# easiri.net
KiCad netlist of a schematic drawn in EAGLE
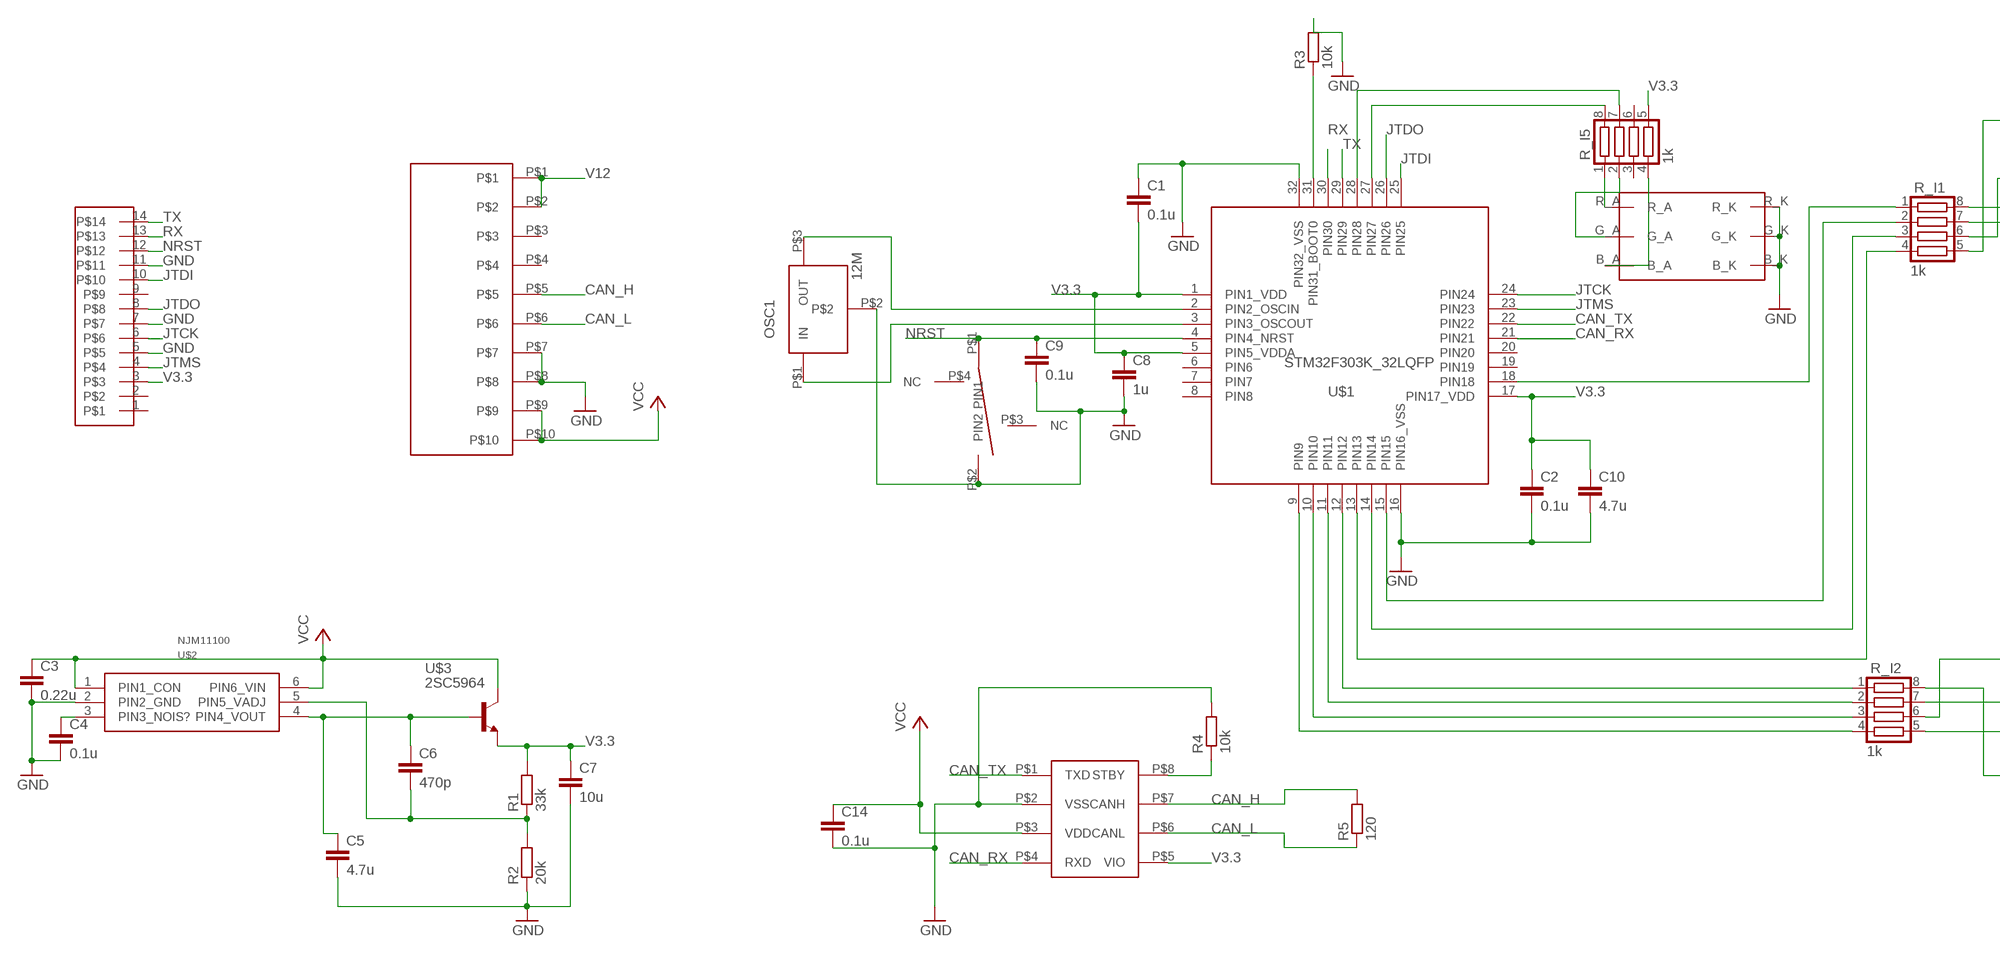
[diagram p0: schematic, sheet 1, part 1 of 2]
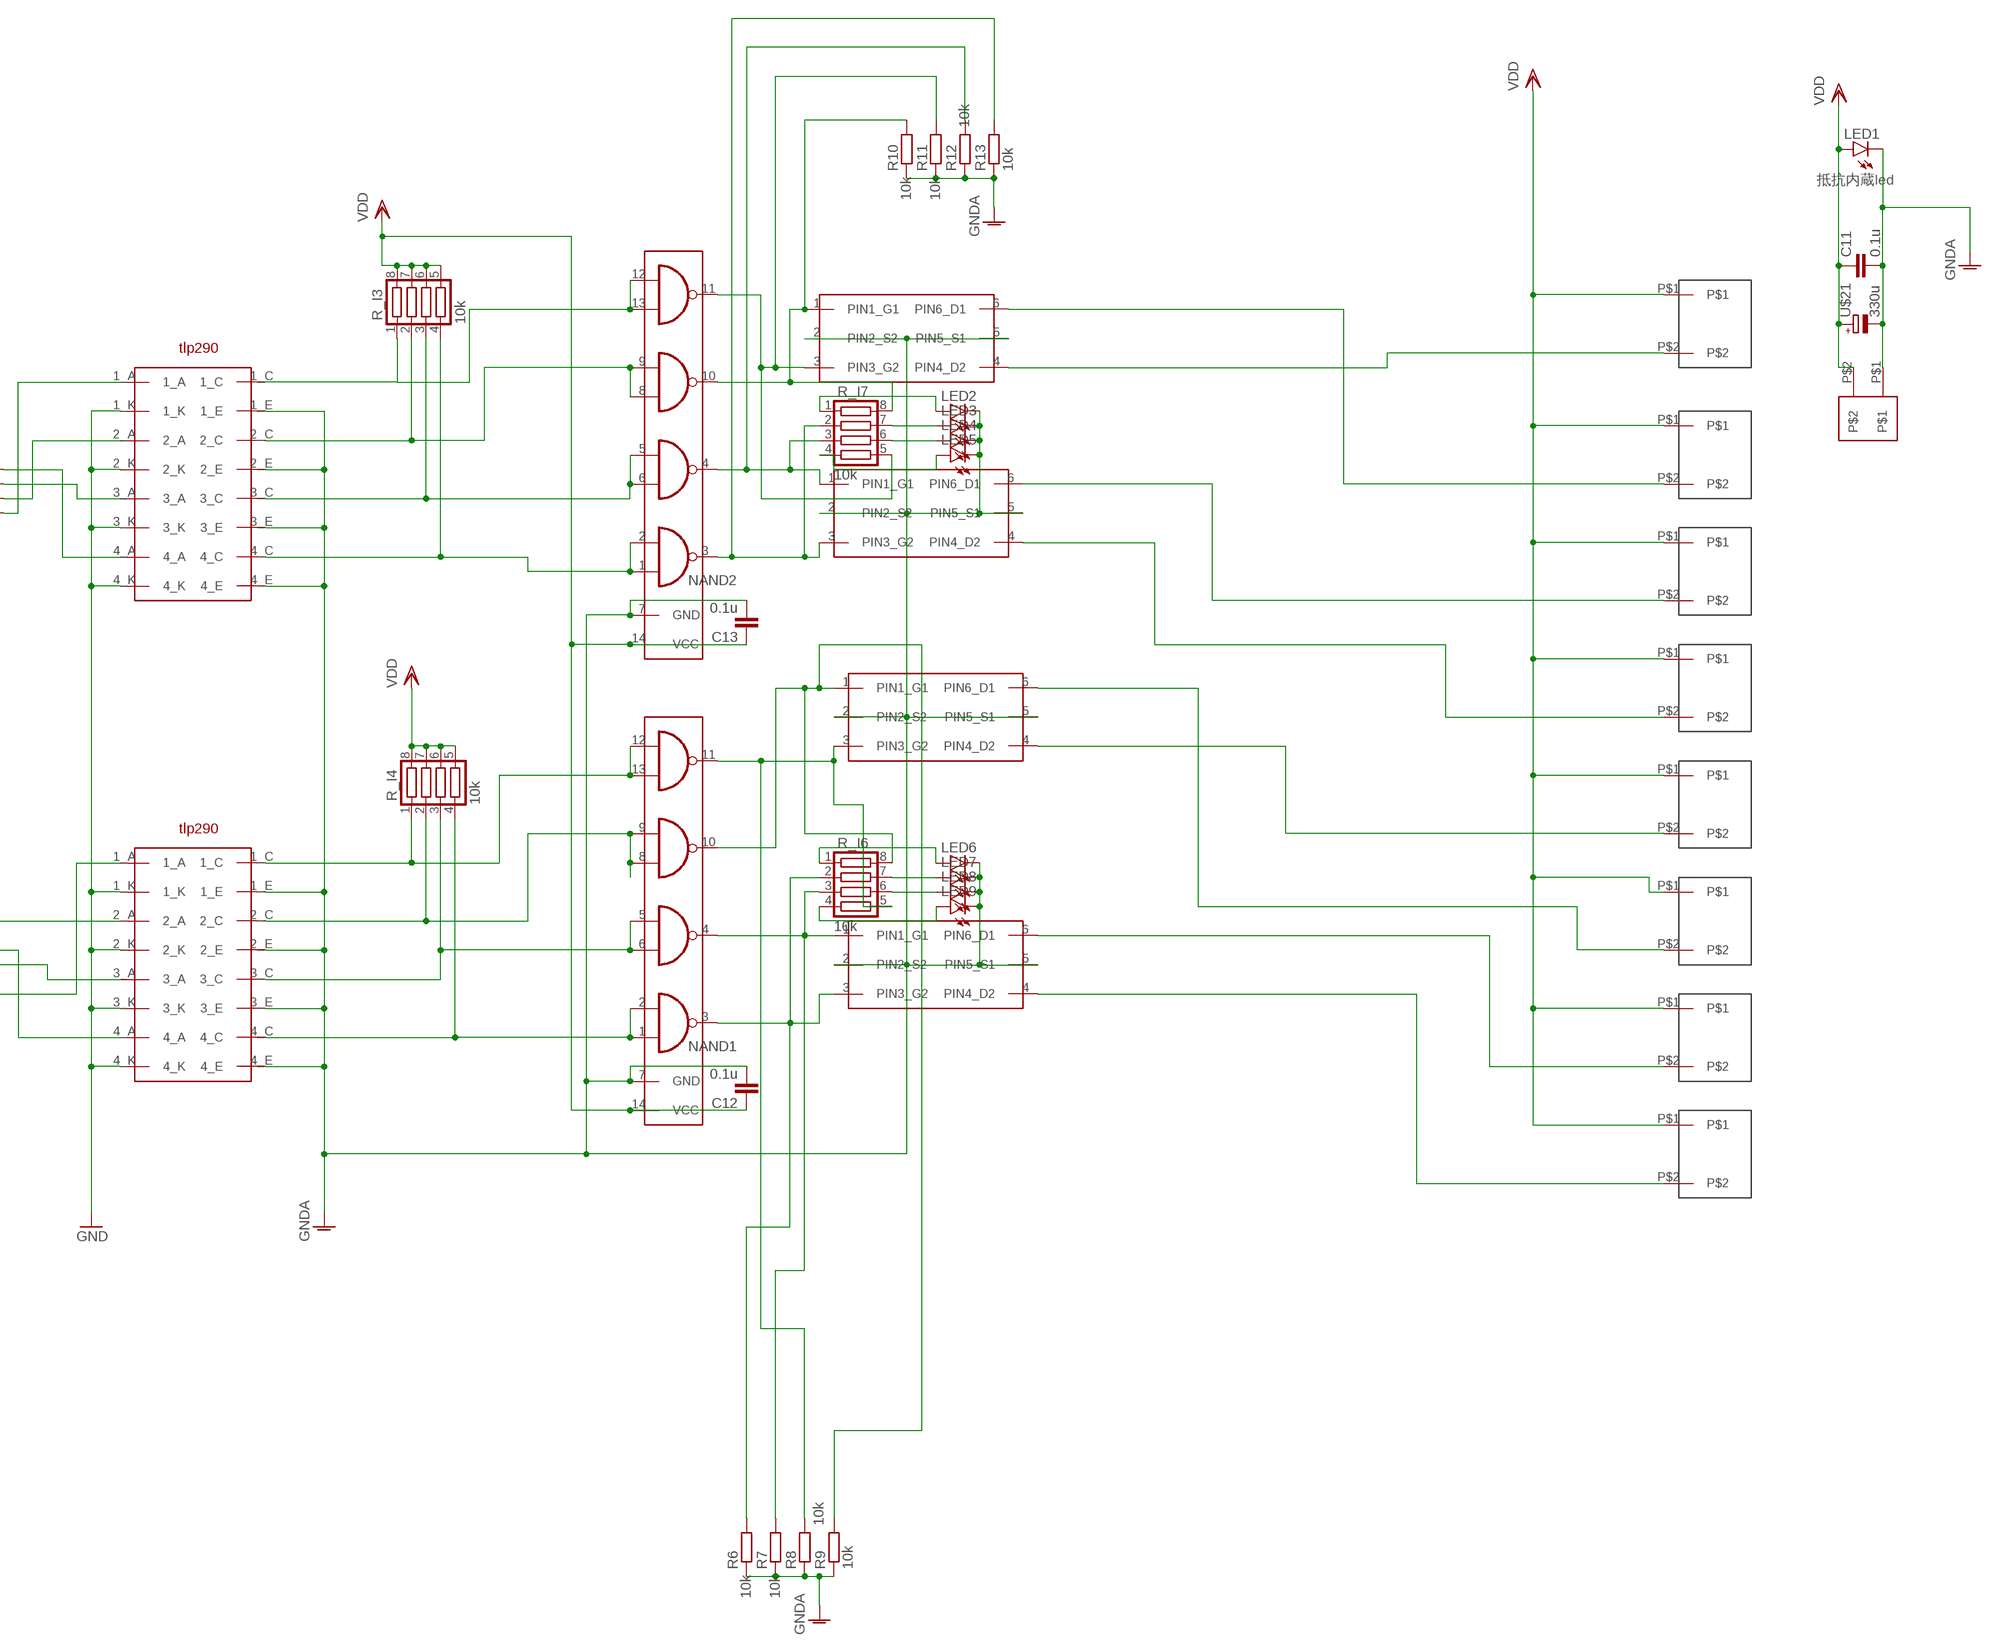
[diagram p1: schematic, sheet 1, part 2 of 2]

(export (version "E")
  (design (tool "Eeschema 10.0.6"))
  (components
    (comp (ref "BOX10P-L2")
      (value "BOX10PBOX10P-L")
      (footprint "eagle-import:BOX10P-L")
      (libsource (lib "eagle-import") (part "BOX10PBOX10P-L"))
    )
    (comp (ref "C1")
      (value "0.1u")
      (footprint "eagle-import:C1608")
      (libsource (lib "eagle-import") (part "C-EUC1608"))
    )
    (comp (ref "C2")
      (value "0.1u")
      (footprint "eagle-import:C1608")
      (libsource (lib "eagle-import") (part "C-EUC1608"))
    )
    (comp (ref "C3")
      (value "0.22u")
      (footprint "eagle-import:C2012")
      (libsource (lib "eagle-import") (part "C-EUC2012"))
    )
    (comp (ref "C4")
      (value "0.1u")
      (footprint "eagle-import:C1608")
      (libsource (lib "eagle-import") (part "C-EUC1608"))
    )
    (comp (ref "C5")
      (value "4.7u")
      (footprint "eagle-import:C2012")
      (libsource (lib "eagle-import") (part "C-EUC2012"))
    )
    (comp (ref "C6")
      (value "470p")
      (footprint "eagle-import:C1608")
      (libsource (lib "eagle-import") (part "C-EUC1608"))
    )
    (comp (ref "C7")
      (value "10u")
      (footprint "eagle-import:C2012")
      (libsource (lib "eagle-import") (part "C-EUC2012"))
    )
    (comp (ref "C8")
      (value "1u")
      (footprint "eagle-import:C1608")
      (libsource (lib "eagle-import") (part "C-EUC1608"))
    )
    (comp (ref "C9")
      (value "0.1u")
      (footprint "eagle-import:C1608")
      (libsource (lib "eagle-import") (part "C-EUC1608"))
    )
    (comp (ref "C10")
      (value "4.7u")
      (footprint "eagle-import:C2012")
      (libsource (lib "eagle-import") (part "C-EUC2012"))
    )
    (comp (ref "C11")
      (value "0.1u")
      (footprint "eagle-import:C1608")
      (libsource (lib "eagle-import") (part "C-EUC1608"))
    )
    (comp (ref "C12")
      (value "0.1u")
      (footprint "eagle-import:C1608")
      (libsource (lib "eagle-import") (part "C-EUC1608"))
    )
    (comp (ref "C13")
      (value "0.1u")
      (footprint "eagle-import:C1608")
      (libsource (lib "eagle-import") (part "C-EUC1608"))
    )
    (comp (ref "C14")
      (value "0.1u")
      (footprint "eagle-import:C1608")
      (libsource (lib "eagle-import") (part "C-EUC1608"))
    )
    (comp (ref "ES1")
      (value "XH_2P")
      (footprint "eagle-import:XH_2P")
      (libsource (lib "eagle-import") (part "XH_2P"))
    )
    (comp (ref "ES2")
      (value "XH_2P")
      (footprint "eagle-import:XH_2P")
      (libsource (lib "eagle-import") (part "XH_2P"))
    )
    (comp (ref "ES3")
      (value "XH_2P")
      (footprint "eagle-import:XH_2P")
      (libsource (lib "eagle-import") (part "XH_2P"))
    )
    (comp (ref "ES4")
      (value "XH_2P")
      (footprint "eagle-import:XH_2P")
      (libsource (lib "eagle-import") (part "XH_2P"))
    )
    (comp (ref "ES5")
      (value "XH_2P")
      (footprint "eagle-import:XH_2P")
      (libsource (lib "eagle-import") (part "XH_2P"))
    )
    (comp (ref "ES6")
      (value "XH_2P")
      (footprint "eagle-import:XH_2P")
      (libsource (lib "eagle-import") (part "XH_2P"))
    )
    (comp (ref "ES7")
      (value "XH_2P")
      (footprint "eagle-import:XH_2P")
      (libsource (lib "eagle-import") (part "XH_2P"))
    )
    (comp (ref "ES8")
      (value "XH_2P")
      (footprint "eagle-import:XH_2P")
      (libsource (lib "eagle-import") (part "XH_2P"))
    )
    (comp (ref "LED1")
      (value "抵抗内蔵led")
      (footprint "eagle-import:LED5MM")
      (libsource (lib "eagle-import") (part "LED5MM"))
    )
    (comp (ref "LED2")
      (value "1608LED")
      (footprint "eagle-import:1608")
      (libsource (lib "eagle-import") (part "1608LED"))
    )
    (comp (ref "LED3")
      (value "1608LED")
      (footprint "eagle-import:1608")
      (libsource (lib "eagle-import") (part "1608LED"))
    )
    (comp (ref "LED4")
      (value "1608LED")
      (footprint "eagle-import:1608")
      (libsource (lib "eagle-import") (part "1608LED"))
    )
    (comp (ref "LED5")
      (value "1608LED")
      (footprint "eagle-import:1608")
      (libsource (lib "eagle-import") (part "1608LED"))
    )
    (comp (ref "LED6")
      (value "1608LED")
      (footprint "eagle-import:1608")
      (libsource (lib "eagle-import") (part "1608LED"))
    )
    (comp (ref "LED7")
      (value "1608LED")
      (footprint "eagle-import:1608")
      (libsource (lib "eagle-import") (part "1608LED"))
    )
    (comp (ref "LED8")
      (value "1608LED")
      (footprint "eagle-import:1608")
      (libsource (lib "eagle-import") (part "1608LED"))
    )
    (comp (ref "LED9")
      (value "1608LED")
      (footprint "eagle-import:1608")
      (libsource (lib "eagle-import") (part "1608LED"))
    )
    (comp (ref "NAND1")
      (value "14PIN_NAND2")
      (footprint "eagle-import:TSSOP14")
      (libsource (lib "eagle-import") (part "14PIN_NAND2"))
    )
    (comp (ref "NAND2")
      (value "14PIN_NAND2")
      (footprint "eagle-import:TSSOP14")
      (libsource (lib "eagle-import") (part "14PIN_NAND2"))
    )
    (comp (ref "OSC1")
      (value "12M")
      (footprint "eagle-import:CSTNE#")
      (libsource (lib "eagle-import") (part "CSTN#"))
    )
    (comp (ref "R1")
      (value "33k")
      (footprint "eagle-import:1608")
      (libsource (lib "eagle-import") (part "R_REG"))
    )
    (comp (ref "R2")
      (value "20k")
      (footprint "eagle-import:1608")
      (libsource (lib "eagle-import") (part "R_REG"))
    )
    (comp (ref "R3")
      (value "10k")
      (footprint "eagle-import:1608")
      (libsource (lib "eagle-import") (part "R_REG"))
    )
    (comp (ref "R4")
      (value "10k")
      (footprint "eagle-import:1608")
      (libsource (lib "eagle-import") (part "R_REG"))
    )
    (comp (ref "R5")
      (value "120")
      (footprint "eagle-import:1608")
      (libsource (lib "eagle-import") (part "R_REG"))
    )
    (comp (ref "R6")
      (value "10k")
      (footprint "eagle-import:1608")
      (libsource (lib "eagle-import") (part "R_REG"))
    )
    (comp (ref "R7")
      (value "10k")
      (footprint "eagle-import:1608")
      (libsource (lib "eagle-import") (part "R_REG"))
    )
    (comp (ref "R8")
      (value "10k")
      (footprint "eagle-import:1608")
      (libsource (lib "eagle-import") (part "R_REG"))
    )
    (comp (ref "R9")
      (value "10k")
      (footprint "eagle-import:1608")
      (libsource (lib "eagle-import") (part "R_REG"))
    )
    (comp (ref "R10")
      (value "10k")
      (footprint "eagle-import:1608")
      (libsource (lib "eagle-import") (part "R_REG"))
    )
    (comp (ref "R11")
      (value "10k")
      (footprint "eagle-import:1608")
      (libsource (lib "eagle-import") (part "R_REG"))
    )
    (comp (ref "R12")
      (value "10k")
      (footprint "eagle-import:1608")
      (libsource (lib "eagle-import") (part "R_REG"))
    )
    (comp (ref "R13")
      (value "10k")
      (footprint "eagle-import:1608")
      (libsource (lib "eagle-import") (part "R_REG"))
    )
    (comp (ref "R_I1")
      (value "1k")
      (footprint "eagle-import:0603X4RESISTOR")
      (libsource (lib "eagle-import") (part "R_SHUGOU"))
    )
    (comp (ref "R_I2")
      (value "1k")
      (footprint "eagle-import:0603X4RESISTOR")
      (libsource (lib "eagle-import") (part "R_SHUGOU"))
    )
    (comp (ref "R_I3")
      (value "10k")
      (footprint "eagle-import:1005X4RESISTOR")
      (libsource (lib "eagle-import") (part "R_SHUGOU2"))
    )
    (comp (ref "R_I4")
      (value "10k")
      (footprint "eagle-import:1005X4RESISTOR")
      (libsource (lib "eagle-import") (part "R_SHUGOU2"))
    )
    (comp (ref "R_I5")
      (value "1k")
      (footprint "eagle-import:0603X4RESISTOR")
      (libsource (lib "eagle-import") (part "R_SHUGOU"))
    )
    (comp (ref "R_I6")
      (value "10k")
      (footprint "eagle-import:1005X4RESISTOR")
      (libsource (lib "eagle-import") (part "R_SHUGOU2"))
    )
    (comp (ref "R_I7")
      (value "10k")
      (footprint "eagle-import:1005X4RESISTOR")
      (libsource (lib "eagle-import") (part "R_SHUGOU2"))
    )
    (comp (ref "U$1")
      (value "STM32F303K_32LQFP")
      (footprint "eagle-import:LQFP32-7X7")
      (libsource (lib "eagle-import") (part "STM32F303K_32LQFP"))
    )
    (comp (ref "U$2")
      (value "NJM11100")
      (footprint "eagle-import:SOT23-6")
      (libsource (lib "eagle-import") (part "NJM11100"))
    )
    (comp (ref "U$3")
      (value "2SC5964")
      (footprint "eagle-import:PCP")
      (libsource (lib "eagle-import") (part "2SC5964"))
    )
    (comp (ref "U$4")
      (value "TAKUTOSUITTI2")
      (footprint "eagle-import:TAKUTOSUITTI2")
      (libsource (lib "eagle-import") (part "TAKUTOSUITTI2"))
    )
    (comp (ref "U$5")
      (value "MCP2562MCP2561-SN")
      (footprint "eagle-import:SOIC8")
      (libsource (lib "eagle-import") (part "MCP2562MCP2561-SN"))
    )
    (comp (ref "U$6")
      (value "TLP290-4")
      (footprint "eagle-import:TLP290")
      (libsource (lib "eagle-import") (part "TLP290-4"))
    )
    (comp (ref "U$7")
      (value "TLP290-4")
      (footprint "eagle-import:TLP290")
      (libsource (lib "eagle-import") (part "TLP290-4"))
    )
    (comp (ref "U$8")
      (value "SSOT6_FET")
      (footprint "eagle-import:SSOT6")
      (libsource (lib "eagle-import") (part "SSOT6_FET"))
    )
    (comp (ref "U$9")
      (value "SSOT6_FET")
      (footprint "eagle-import:SSOT6")
      (libsource (lib "eagle-import") (part "SSOT6_FET"))
    )
    (comp (ref "U$10")
      (value "SSOT6_FET")
      (footprint "eagle-import:SSOT6")
      (libsource (lib "eagle-import") (part "SSOT6_FET"))
    )
    (comp (ref "U$11")
      (value "SSOT6_FET")
      (footprint "eagle-import:SSOT6")
      (libsource (lib "eagle-import") (part "SSOT6_FET"))
    )
    (comp (ref "U$12")
      (value "YUROBLOCK2")
      (footprint "eagle-import:YUROBLOCK2")
      (libsource (lib "eagle-import") (part "YUROBLOCK2"))
    )
    (comp (ref "U$21")
      (value "330u")
      (footprint "eagle-import:1014CAPA")
      (libsource (lib "eagle-import") (part "C_DEKAI"))
    )
    (comp (ref "U$22")
      (value "BOX14P")
      (footprint "eagle-import:CON_HEDA14P_1.27")
      (libsource (lib "eagle-import") (part "BOX14P"))
    )
    (comp (ref "U$23")
      (value "RGB_LED")
      (footprint "eagle-import:RGB_LED")
      (libsource (lib "eagle-import") (part "RGB_LED"))
    )
  )
  (nets
    (net (code "1") (name "/CAN_H") (class "Default")
      (node (ref "BOX10P-L2") (pin "P$5") (pinfunction "P$5_P$5") (pintype "bidirectional"))
      (node (ref "R5") (pin "2") (pinfunction "2_2") (pintype "passive"))
      (node (ref "U$5") (pin "P$7") (pinfunction "CANH_P$7") (pintype "bidirectional"))
    )
    (net (code "2") (name "/CAN_L") (class "Default")
      (node (ref "BOX10P-L2") (pin "P$6") (pinfunction "P$6_P$6") (pintype "bidirectional"))
      (node (ref "R5") (pin "1") (pinfunction "1_1") (pintype "passive"))
      (node (ref "U$5") (pin "P$6") (pinfunction "CANL_P$6") (pintype "bidirectional"))
    )
    (net (code "3") (name "/CAN_RX") (class "Default")
      (node (ref "U$1") (pin "21") (pinfunction "PIN21_21") (pintype "bidirectional"))
      (node (ref "U$5") (pin "P$4") (pinfunction "RXD_P$4") (pintype "bidirectional"))
    )
    (net (code "4") (name "/CAN_TX") (class "Default")
      (node (ref "U$1") (pin "22") (pinfunction "PIN22_22") (pintype "bidirectional"))
      (node (ref "U$5") (pin "P$1") (pinfunction "TXD_P$1") (pintype "bidirectional"))
    )
    (net (code "5") (name "/JTCK") (class "Default")
      (node (ref "U$1") (pin "24") (pinfunction "PIN24_24") (pintype "bidirectional"))
      (node (ref "U$22") (pin "6") (pinfunction "P$6_6") (pintype "bidirectional"))
    )
    (net (code "6") (name "/JTDI") (class "Default")
      (node (ref "U$1") (pin "25") (pinfunction "PIN25_25") (pintype "bidirectional"))
      (node (ref "U$22") (pin "10") (pinfunction "P$10_10") (pintype "bidirectional"))
    )
    (net (code "7") (name "/JTDO") (class "Default")
      (node (ref "U$1") (pin "26") (pinfunction "PIN26_26") (pintype "bidirectional"))
      (node (ref "U$22") (pin "8") (pinfunction "P$8_8") (pintype "bidirectional"))
    )
    (net (code "8") (name "/JTMS") (class "Default")
      (node (ref "U$1") (pin "23") (pinfunction "PIN23_23") (pintype "bidirectional"))
      (node (ref "U$22") (pin "4") (pinfunction "P$4_4") (pintype "bidirectional"))
    )
    (net (code "9") (name "/NRST") (class "Default")
      (node (ref "C9") (pin "1") (pinfunction "1_1") (pintype "passive"))
      (node (ref "U$1") (pin "4") (pinfunction "PIN4_NRST_4") (pintype "bidirectional"))
      (node (ref "U$22") (pin "12") (pinfunction "P$12_12") (pintype "bidirectional"))
      (node (ref "U$4") (pin "P$1") (pinfunction "PIN1_P$1") (pintype "bidirectional"))
    )
    (net (code "10") (name "/RX") (class "Default")
      (node (ref "U$1") (pin "30") (pinfunction "PIN30_30") (pintype "bidirectional"))
      (node (ref "U$22") (pin "13") (pinfunction "P$13_13") (pintype "bidirectional"))
    )
    (net (code "11") (name "/TX") (class "Default")
      (node (ref "U$1") (pin "29") (pinfunction "PIN29_29") (pintype "bidirectional"))
      (node (ref "U$22") (pin "14") (pinfunction "P$14_14") (pintype "bidirectional"))
    )
    (net (code "12") (name "/V3.3") (class "Default")
      (node (ref "C1") (pin "2") (pinfunction "2_2") (pintype "passive"))
      (node (ref "C10") (pin "1") (pinfunction "1_1") (pintype "passive"))
      (node (ref "C2") (pin "1") (pinfunction "1_1") (pintype "passive"))
      (node (ref "C7") (pin "1") (pinfunction "1_1") (pintype "passive"))
      (node (ref "C8") (pin "1") (pinfunction "1_1") (pintype "passive"))
      (node (ref "R1") (pin "2") (pinfunction "2_2") (pintype "passive"))
      (node (ref "R_I5") (pin "5") (pinfunction "5_5") (pintype "passive"))
      (node (ref "U$1") (pin "1") (pinfunction "PIN1_VDD_1") (pintype "bidirectional"))
      (node (ref "U$1") (pin "17") (pinfunction "PIN17_VDD_17") (pintype "bidirectional"))
      (node (ref "U$1") (pin "5") (pinfunction "PIN5_VDDA_5") (pintype "bidirectional"))
      (node (ref "U$22") (pin "3") (pinfunction "P$3_3") (pintype "bidirectional"))
      (node (ref "U$3") (pin "3") (pinfunction "E_3") (pintype "passive"))
      (node (ref "U$5") (pin "P$5") (pinfunction "VIO_P$5") (pintype "bidirectional"))
    )
    (net (code "13") (name "/V12") (class "Default")
      (node (ref "BOX10P-L2") (pin "P$1") (pinfunction "P$1_P$1") (pintype "bidirectional"))
      (node (ref "BOX10P-L2") (pin "P$2") (pinfunction "P$2_P$2") (pintype "bidirectional"))
    )
    (net (code "14") (name "GND") (class "Default")
      (node (ref "BOX10P-L2") (pin "P$7") (pinfunction "P$7_P$7") (pintype "bidirectional"))
      (node (ref "BOX10P-L2") (pin "P$8") (pinfunction "P$8_P$8") (pintype "bidirectional"))
      (node (ref "C1") (pin "1") (pinfunction "1_1") (pintype "passive"))
      (node (ref "C10") (pin "2") (pinfunction "2_2") (pintype "passive"))
      (node (ref "C14") (pin "2") (pinfunction "2_2") (pintype "passive"))
      (node (ref "C2") (pin "2") (pinfunction "2_2") (pintype "passive"))
      (node (ref "C3") (pin "2") (pinfunction "2_2") (pintype "passive"))
      (node (ref "C4") (pin "2") (pinfunction "2_2") (pintype "passive"))
      (node (ref "C5") (pin "2") (pinfunction "2_2") (pintype "passive"))
      (node (ref "C7") (pin "2") (pinfunction "2_2") (pintype "passive"))
      (node (ref "C8") (pin "2") (pinfunction "2_2") (pintype "passive"))
      (node (ref "C9") (pin "2") (pinfunction "2_2") (pintype "passive"))
      (node (ref "OSC1") (pin "P$2") (pinfunction "P$2_P$2") (pintype "bidirectional"))
      (node (ref "R2") (pin "1") (pinfunction "1_1") (pintype "passive"))
      (node (ref "R3") (pin "2") (pinfunction "2_2") (pintype "passive"))
      (node (ref "R4") (pin "2") (pinfunction "2_2") (pintype "passive"))
      (node (ref "U$1") (pin "16") (pinfunction "PIN16_VSS_16") (pintype "bidirectional"))
      (node (ref "U$1") (pin "32") (pinfunction "PIN32_VSS_32") (pintype "bidirectional"))
      (node (ref "U$2") (pin "2") (pinfunction "PIN2_GND_2") (pintype "bidirectional"))
      (node (ref "U$22") (pin "11") (pinfunction "P$11_11") (pintype "bidirectional"))
      (node (ref "U$22") (pin "5") (pinfunction "P$5_5") (pintype "bidirectional"))
      (node (ref "U$22") (pin "7") (pinfunction "P$7_7") (pintype "bidirectional"))
      (node (ref "U$23") (pin "B_K") (pinfunction "B_K_B_K") (pintype "bidirectional"))
      (node (ref "U$23") (pin "G_K") (pinfunction "G_K_G_K") (pintype "bidirectional"))
      (node (ref "U$23") (pin "R_K") (pinfunction "R_K_R_K") (pintype "bidirectional"))
      (node (ref "U$4") (pin "P$2") (pinfunction "PIN2_P$2") (pintype "bidirectional"))
      (node (ref "U$5") (pin "P$2") (pinfunction "VSS_P$2") (pintype "bidirectional"))
      (node (ref "U$6") (pin "1_K") (pinfunction "1_K_1_K") (pintype "bidirectional"))
      (node (ref "U$6") (pin "2_K") (pinfunction "2_K_2_K") (pintype "bidirectional"))
      (node (ref "U$6") (pin "3_K") (pinfunction "3_K_3_K") (pintype "bidirectional"))
      (node (ref "U$6") (pin "4_K") (pinfunction "4_K_4_K") (pintype "bidirectional"))
      (node (ref "U$7") (pin "1_K") (pinfunction "1_K_1_K") (pintype "bidirectional"))
      (node (ref "U$7") (pin "2_K") (pinfunction "2_K_2_K") (pintype "bidirectional"))
      (node (ref "U$7") (pin "3_K") (pinfunction "3_K_3_K") (pintype "bidirectional"))
      (node (ref "U$7") (pin "4_K") (pinfunction "4_K_4_K") (pintype "bidirectional"))
    )
    (net (code "15") (name "GNDA") (class "Default")
      (node (ref "C11") (pin "2") (pinfunction "2_2") (pintype "passive"))
      (node (ref "C12") (pin "2") (pinfunction "2_2") (pintype "passive"))
      (node (ref "C13") (pin "2") (pinfunction "2_2") (pintype "passive"))
      (node (ref "LED1") (pin "K") (pinfunction "C_K") (pintype "passive"))
      (node (ref "LED2") (pin "K") (pinfunction "K_K") (pintype "passive"))
      (node (ref "LED3") (pin "K") (pinfunction "K_K") (pintype "passive"))
      (node (ref "LED4") (pin "K") (pinfunction "K_K") (pintype "passive"))
      (node (ref "LED5") (pin "K") (pinfunction "K_K") (pintype "passive"))
      (node (ref "LED6") (pin "K") (pinfunction "K_K") (pintype "passive"))
      (node (ref "LED7") (pin "K") (pinfunction "K_K") (pintype "passive"))
      (node (ref "LED8") (pin "K") (pinfunction "K_K") (pintype "passive"))
      (node (ref "LED9") (pin "K") (pinfunction "K_K") (pintype "passive"))
      (node (ref "NAND1") (pin "7") (pinfunction "GND_7") (pintype "bidirectional"))
      (node (ref "NAND2") (pin "7") (pinfunction "GND_7") (pintype "bidirectional"))
      (node (ref "R10") (pin "1") (pinfunction "1_1") (pintype "passive"))
      (node (ref "R11") (pin "1") (pinfunction "1_1") (pintype "passive"))
      (node (ref "R12") (pin "1") (pinfunction "1_1") (pintype "passive"))
      (node (ref "R13") (pin "1") (pinfunction "1_1") (pintype "passive"))
      (node (ref "R6") (pin "1") (pinfunction "1_1") (pintype "passive"))
      (node (ref "R7") (pin "1") (pinfunction "1_1") (pintype "passive"))
      (node (ref "R8") (pin "1") (pinfunction "1_1") (pintype "passive"))
      (node (ref "R9") (pin "1") (pinfunction "1_1") (pintype "passive"))
      (node (ref "U$10") (pin "2") (pinfunction "PIN2_S2_2") (pintype "bidirectional"))
      (node (ref "U$10") (pin "5") (pinfunction "PIN5_S1_5") (pintype "bidirectional"))
      (node (ref "U$11") (pin "2") (pinfunction "PIN2_S2_2") (pintype "bidirectional"))
      (node (ref "U$11") (pin "5") (pinfunction "PIN5_S1_5") (pintype "bidirectional"))
      (node (ref "U$12") (pin "P$1") (pinfunction "P$1_P$1") (pintype "bidirectional"))
      (node (ref "U$21") (pin "-") (pinfunction "-_-") (pintype "passive"))
      (node (ref "U$6") (pin "1_E") (pinfunction "1_E_1_E") (pintype "bidirectional"))
      (node (ref "U$6") (pin "2_E") (pinfunction "2_E_2_E") (pintype "bidirectional"))
      (node (ref "U$6") (pin "3_E") (pinfunction "3_E_3_E") (pintype "bidirectional"))
      (node (ref "U$6") (pin "4_E") (pinfunction "4_E_4_E") (pintype "bidirectional"))
      (node (ref "U$7") (pin "1_E") (pinfunction "1_E_1_E") (pintype "bidirectional"))
      (node (ref "U$7") (pin "2_E") (pinfunction "2_E_2_E") (pintype "bidirectional"))
      (node (ref "U$7") (pin "3_E") (pinfunction "3_E_3_E") (pintype "bidirectional"))
      (node (ref "U$7") (pin "4_E") (pinfunction "4_E_4_E") (pintype "bidirectional"))
      (node (ref "U$8") (pin "2") (pinfunction "PIN2_S2_2") (pintype "bidirectional"))
      (node (ref "U$8") (pin "5") (pinfunction "PIN5_S1_5") (pintype "bidirectional"))
      (node (ref "U$9") (pin "2") (pinfunction "PIN2_S2_2") (pintype "bidirectional"))
      (node (ref "U$9") (pin "5") (pinfunction "PIN5_S1_5") (pintype "bidirectional"))
    )
    (net (code "16") (name "Net-(LED2-PadA)") (class "Default")
      (node (ref "LED2") (pin "A") (pinfunction "A_A") (pintype "passive"))
      (node (ref "R_I7") (pin "1") (pinfunction "1_1") (pintype "passive"))
    )
    (net (code "17") (name "Net-(LED3-PadA)") (class "Default")
      (node (ref "LED3") (pin "A") (pinfunction "A_A") (pintype "passive"))
      (node (ref "R_I7") (pin "7") (pinfunction "7_7") (pintype "passive"))
    )
    (net (code "18") (name "Net-(LED4-PadA)") (class "Default")
      (node (ref "LED4") (pin "A") (pinfunction "A_A") (pintype "passive"))
      (node (ref "R_I7") (pin "6") (pinfunction "6_6") (pintype "passive"))
    )
    (net (code "19") (name "Net-(LED5-PadA)") (class "Default")
      (node (ref "LED5") (pin "A") (pinfunction "A_A") (pintype "passive"))
      (node (ref "R_I7") (pin "4") (pinfunction "4_4") (pintype "passive"))
    )
    (net (code "20") (name "Net-(LED6-PadA)") (class "Default")
      (node (ref "LED6") (pin "A") (pinfunction "A_A") (pintype "passive"))
      (node (ref "R_I6") (pin "1") (pinfunction "1_1") (pintype "passive"))
    )
    (net (code "21") (name "Net-(LED7-PadA)") (class "Default")
      (node (ref "LED7") (pin "A") (pinfunction "A_A") (pintype "passive"))
      (node (ref "R_I6") (pin "7") (pinfunction "7_7") (pintype "passive"))
    )
    (net (code "22") (name "Net-(LED8-PadA)") (class "Default")
      (node (ref "LED8") (pin "A") (pinfunction "A_A") (pintype "passive"))
      (node (ref "R_I6") (pin "6") (pinfunction "6_6") (pintype "passive"))
    )
    (net (code "23") (name "Net-(LED9-PadA)") (class "Default")
      (node (ref "LED9") (pin "A") (pinfunction "A_A") (pintype "passive"))
      (node (ref "R_I6") (pin "4") (pinfunction "4_4") (pintype "passive"))
    )
    (net (code "24") (name "Net-(NAND1-1A)") (class "Default")
      (node (ref "NAND1") (pin "1") (pinfunction "1A_1") (pintype "input"))
      (node (ref "NAND1") (pin "2") (pinfunction "1B_2") (pintype "input"))
      (node (ref "R_I4") (pin "4") (pinfunction "4_4") (pintype "passive"))
      (node (ref "U$7") (pin "4_C") (pinfunction "4_C_4_C") (pintype "bidirectional"))
    )
    (net (code "25") (name "Net-(NAND1-1Y)") (class "Default")
      (node (ref "NAND1") (pin "3") (pinfunction "1Y_3") (pintype "output"))
      (node (ref "R6") (pin "2") (pinfunction "2_2") (pintype "passive"))
      (node (ref "R_I6") (pin "2") (pinfunction "2_2") (pintype "passive"))
      (node (ref "U$11") (pin "3") (pinfunction "PIN3_G2_3") (pintype "bidirectional"))
    )
    (net (code "26") (name "Net-(NAND1-2A)") (class "Default")
      (node (ref "NAND1") (pin "5") (pinfunction "2B_5") (pintype "input"))
      (node (ref "NAND1") (pin "6") (pinfunction "2A_6") (pintype "input"))
      (node (ref "R_I4") (pin "3") (pinfunction "3_3") (pintype "passive"))
      (node (ref "U$7") (pin "3_C") (pinfunction "3_C_3_C") (pintype "bidirectional"))
    )
    (net (code "27") (name "Net-(NAND1-2Y)") (class "Default")
      (node (ref "NAND1") (pin "4") (pinfunction "2Y_4") (pintype "output"))
      (node (ref "R7") (pin "2") (pinfunction "2_2") (pintype "passive"))
      (node (ref "R_I6") (pin "3") (pinfunction "3_3") (pintype "passive"))
      (node (ref "U$11") (pin "1") (pinfunction "PIN1_G1_1") (pintype "bidirectional"))
    )
    (net (code "28") (name "Net-(NAND1-3A)") (class "Default")
      (node (ref "NAND1") (pin "8") (pinfunction "3A_8") (pintype "input"))
      (node (ref "NAND1") (pin "9") (pinfunction "3B_9") (pintype "input"))
      (node (ref "R_I4") (pin "2") (pinfunction "2_2") (pintype "passive"))
      (node (ref "U$7") (pin "2_C") (pinfunction "2_C_2_C") (pintype "bidirectional"))
    )
    (net (code "29") (name "Net-(NAND1-3Y)") (class "Default")
      (node (ref "NAND1") (pin "10") (pinfunction "3Y_10") (pintype "output"))
      (node (ref "R9") (pin "2") (pinfunction "2_2") (pintype "passive"))
      (node (ref "R_I6") (pin "8") (pinfunction "8_8") (pintype "passive"))
      (node (ref "U$10") (pin "1") (pinfunction "PIN1_G1_1") (pintype "bidirectional"))
    )
    (net (code "30") (name "Net-(NAND1-4A)") (class "Default")
      (node (ref "NAND1") (pin "12") (pinfunction "4B_12") (pintype "input"))
      (node (ref "NAND1") (pin "13") (pinfunction "4A_13") (pintype "input"))
      (node (ref "R_I4") (pin "1") (pinfunction "1_1") (pintype "passive"))
      (node (ref "U$7") (pin "1_C") (pinfunction "1_C_1_C") (pintype "bidirectional"))
    )
    (net (code "31") (name "Net-(NAND1-4Y)") (class "Default")
      (node (ref "NAND1") (pin "11") (pinfunction "4Y_11") (pintype "output"))
      (node (ref "R8") (pin "2") (pinfunction "2_2") (pintype "passive"))
      (node (ref "R_I6") (pin "5") (pinfunction "5_5") (pintype "passive"))
      (node (ref "U$10") (pin "3") (pinfunction "PIN3_G2_3") (pintype "bidirectional"))
    )
    (net (code "32") (name "Net-(NAND2-1A)") (class "Default")
      (node (ref "NAND2") (pin "1") (pinfunction "1A_1") (pintype "input"))
      (node (ref "NAND2") (pin "2") (pinfunction "1B_2") (pintype "input"))
      (node (ref "R_I3") (pin "4") (pinfunction "4_4") (pintype "passive"))
      (node (ref "U$6") (pin "4_C") (pinfunction "4_C_4_C") (pintype "bidirectional"))
    )
    (net (code "33") (name "Net-(NAND2-1Y)") (class "Default")
      (node (ref "NAND2") (pin "3") (pinfunction "1Y_3") (pintype "output"))
      (node (ref "R13") (pin "2") (pinfunction "2_2") (pintype "passive"))
      (node (ref "R_I7") (pin "2") (pinfunction "2_2") (pintype "passive"))
      (node (ref "U$9") (pin "3") (pinfunction "PIN3_G2_3") (pintype "bidirectional"))
    )
    (net (code "34") (name "Net-(NAND2-2A)") (class "Default")
      (node (ref "NAND2") (pin "5") (pinfunction "2B_5") (pintype "input"))
      (node (ref "NAND2") (pin "6") (pinfunction "2A_6") (pintype "input"))
      (node (ref "R_I3") (pin "3") (pinfunction "3_3") (pintype "passive"))
      (node (ref "U$6") (pin "3_C") (pinfunction "3_C_3_C") (pintype "bidirectional"))
    )
    (net (code "35") (name "Net-(NAND2-2Y)") (class "Default")
      (node (ref "NAND2") (pin "4") (pinfunction "2Y_4") (pintype "output"))
      (node (ref "R12") (pin "2") (pinfunction "2_2") (pintype "passive"))
      (node (ref "R_I7") (pin "3") (pinfunction "3_3") (pintype "passive"))
      (node (ref "U$9") (pin "1") (pinfunction "PIN1_G1_1") (pintype "bidirectional"))
    )
    (net (code "36") (name "Net-(NAND2-3A)") (class "Default")
      (node (ref "NAND2") (pin "8") (pinfunction "3A_8") (pintype "input"))
      (node (ref "NAND2") (pin "9") (pinfunction "3B_9") (pintype "input"))
      (node (ref "R_I3") (pin "2") (pinfunction "2_2") (pintype "passive"))
      (node (ref "U$6") (pin "2_C") (pinfunction "2_C_2_C") (pintype "bidirectional"))
    )
    (net (code "37") (name "Net-(NAND2-3Y)") (class "Default")
      (node (ref "NAND2") (pin "10") (pinfunction "3Y_10") (pintype "output"))
      (node (ref "R10") (pin "2") (pinfunction "2_2") (pintype "passive"))
      (node (ref "R_I7") (pin "8") (pinfunction "8_8") (pintype "passive"))
      (node (ref "U$8") (pin "1") (pinfunction "PIN1_G1_1") (pintype "bidirectional"))
    )
    (net (code "38") (name "Net-(NAND2-4A)") (class "Default")
      (node (ref "NAND2") (pin "12") (pinfunction "4B_12") (pintype "input"))
      (node (ref "NAND2") (pin "13") (pinfunction "4A_13") (pintype "input"))
      (node (ref "R_I3") (pin "1") (pinfunction "1_1") (pintype "passive"))
      (node (ref "U$6") (pin "1_C") (pinfunction "1_C_1_C") (pintype "bidirectional"))
    )
    (net (code "39") (name "Net-(NAND2-4Y)") (class "Default")
      (node (ref "NAND2") (pin "11") (pinfunction "4Y_11") (pintype "output"))
      (node (ref "R11") (pin "2") (pinfunction "2_2") (pintype "passive"))
      (node (ref "R_I7") (pin "5") (pinfunction "5_5") (pintype "passive"))
      (node (ref "U$8") (pin "3") (pinfunction "PIN3_G2_3") (pintype "bidirectional"))
    )
    (net (code "40") (name "Net-(OSC1-IN)") (class "Default")
      (node (ref "OSC1") (pin "P$1") (pinfunction "IN_P$1") (pintype "bidirectional"))
      (node (ref "U$1") (pin "3") (pinfunction "PIN3_OSCOUT_3") (pintype "bidirectional"))
    )
    (net (code "41") (name "Net-(OSC1-OUT)") (class "Default")
      (node (ref "OSC1") (pin "P$3") (pinfunction "OUT_P$3") (pintype "bidirectional"))
      (node (ref "U$1") (pin "2") (pinfunction "PIN2_OSCIN_2") (pintype "bidirectional"))
    )
    (net (code "42") (name "Net-(R_I1-Pad5)") (class "Default")
      (node (ref "R_I1") (pin "5") (pinfunction "5_5") (pintype "passive"))
      (node (ref "U$6") (pin "1_A") (pinfunction "1_A_1_A") (pintype "bidirectional"))
    )
    (net (code "43") (name "Net-(R_I1-Pad6)") (class "Default")
      (node (ref "R_I1") (pin "6") (pinfunction "6_6") (pintype "passive"))
      (node (ref "U$6") (pin "2_A") (pinfunction "2_A_2_A") (pintype "bidirectional"))
    )
    (net (code "44") (name "Net-(R_I1-Pad7)") (class "Default")
      (node (ref "R_I1") (pin "7") (pinfunction "7_7") (pintype "passive"))
      (node (ref "U$6") (pin "3_A") (pinfunction "3_A_3_A") (pintype "bidirectional"))
    )
    (net (code "45") (name "Net-(R_I1-Pad8)") (class "Default")
      (node (ref "R_I1") (pin "8") (pinfunction "8_8") (pintype "passive"))
      (node (ref "U$6") (pin "4_A") (pinfunction "4_A_4_A") (pintype "bidirectional"))
    )
    (net (code "46") (name "Net-(R_I2-Pad5)") (class "Default")
      (node (ref "R_I2") (pin "5") (pinfunction "5_5") (pintype "passive"))
      (node (ref "U$7") (pin "1_A") (pinfunction "1_A_1_A") (pintype "bidirectional"))
    )
    (net (code "47") (name "Net-(R_I2-Pad6)") (class "Default")
      (node (ref "R_I2") (pin "6") (pinfunction "6_6") (pintype "passive"))
      (node (ref "U$7") (pin "2_A") (pinfunction "2_A_2_A") (pintype "bidirectional"))
    )
    (net (code "48") (name "Net-(R_I2-Pad7)") (class "Default")
      (node (ref "R_I2") (pin "7") (pinfunction "7_7") (pintype "passive"))
      (node (ref "U$7") (pin "3_A") (pinfunction "3_A_3_A") (pintype "bidirectional"))
    )
    (net (code "49") (name "Net-(R_I2-Pad8)") (class "Default")
      (node (ref "R_I2") (pin "8") (pinfunction "8_8") (pintype "passive"))
      (node (ref "U$7") (pin "4_A") (pinfunction "4_A_4_A") (pintype "bidirectional"))
    )
    (net (code "50") (name "Net-(R_I5-Pad1)") (class "Default")
      (node (ref "R_I5") (pin "1") (pinfunction "1_1") (pintype "passive"))
      (node (ref "U$23") (pin "R_A") (pinfunction "R_A_R_A") (pintype "bidirectional"))
    )
    (net (code "51") (name "Net-(R_I5-Pad2)") (class "Default")
      (node (ref "R_I5") (pin "2") (pinfunction "2_2") (pintype "passive"))
      (node (ref "U$23") (pin "G_A") (pinfunction "G_A_G_A") (pintype "bidirectional"))
    )
    (net (code "52") (name "Net-(R_I5-Pad4)") (class "Default")
      (node (ref "R_I5") (pin "4") (pinfunction "4_4") (pintype "passive"))
      (node (ref "U$23") (pin "B_A") (pinfunction "B_A_B_A") (pintype "bidirectional"))
    )
    (net (code "53") (name "Net-(U$1-PIN9)") (class "Default")
      (node (ref "R_I2") (pin "4") (pinfunction "4_4") (pintype "passive"))
      (node (ref "U$1") (pin "9") (pinfunction "PIN9_9") (pintype "bidirectional"))
    )
    (net (code "54") (name "Net-(U$1-PIN10)") (class "Default")
      (node (ref "R_I2") (pin "3") (pinfunction "3_3") (pintype "passive"))
      (node (ref "U$1") (pin "10") (pinfunction "PIN10_10") (pintype "bidirectional"))
    )
    (net (code "55") (name "Net-(U$1-PIN11)") (class "Default")
      (node (ref "R_I2") (pin "2") (pinfunction "2_2") (pintype "passive"))
      (node (ref "U$1") (pin "11") (pinfunction "PIN11_11") (pintype "bidirectional"))
    )
    (net (code "56") (name "Net-(U$1-PIN12)") (class "Default")
      (node (ref "R_I2") (pin "1") (pinfunction "1_1") (pintype "passive"))
      (node (ref "U$1") (pin "12") (pinfunction "PIN12_12") (pintype "bidirectional"))
    )
    (net (code "57") (name "Net-(U$1-PIN13)") (class "Default")
      (node (ref "R_I1") (pin "4") (pinfunction "4_4") (pintype "passive"))
      (node (ref "U$1") (pin "13") (pinfunction "PIN13_13") (pintype "bidirectional"))
    )
    (net (code "58") (name "Net-(U$1-PIN14)") (class "Default")
      (node (ref "R_I1") (pin "3") (pinfunction "3_3") (pintype "passive"))
      (node (ref "U$1") (pin "14") (pinfunction "PIN14_14") (pintype "bidirectional"))
    )
    (net (code "59") (name "Net-(U$1-PIN15)") (class "Default")
      (node (ref "R_I1") (pin "2") (pinfunction "2_2") (pintype "passive"))
      (node (ref "U$1") (pin "15") (pinfunction "PIN15_15") (pintype "bidirectional"))
    )
    (net (code "60") (name "Net-(U$1-PIN18)") (class "Default")
      (node (ref "R_I1") (pin "1") (pinfunction "1_1") (pintype "passive"))
      (node (ref "U$1") (pin "18") (pinfunction "PIN18_18") (pintype "bidirectional"))
    )
    (net (code "61") (name "Net-(U$1-PIN27)") (class "Default")
      (node (ref "R_I5") (pin "8") (pinfunction "8_8") (pintype "passive"))
      (node (ref "U$1") (pin "27") (pinfunction "PIN27_27") (pintype "bidirectional"))
    )
    (net (code "62") (name "Net-(U$1-PIN28)") (class "Default")
      (node (ref "R_I5") (pin "7") (pinfunction "7_7") (pintype "passive"))
      (node (ref "U$1") (pin "28") (pinfunction "PIN28_28") (pintype "bidirectional"))
    )
    (net (code "63") (name "Net-(U$1-PIN31_BOOT0)") (class "Default")
      (node (ref "R3") (pin "1") (pinfunction "1_1") (pintype "passive"))
      (node (ref "U$1") (pin "31") (pinfunction "PIN31_BOOT0_31") (pintype "bidirectional"))
    )
    (net (code "64") (name "Net-(U$2-PIN3_NOIS?)") (class "Default")
      (node (ref "C4") (pin "1") (pinfunction "1_1") (pintype "passive"))
      (node (ref "U$2") (pin "3") (pinfunction "PIN3_NOIS?_3") (pintype "bidirectional"))
    )
    (net (code "65") (name "Net-(U$2-PIN4_VOUT)") (class "Default")
      (node (ref "C5") (pin "1") (pinfunction "1_1") (pintype "passive"))
      (node (ref "C6") (pin "1") (pinfunction "1_1") (pintype "passive"))
      (node (ref "U$2") (pin "4") (pinfunction "PIN4_VOUT_4") (pintype "bidirectional"))
      (node (ref "U$3") (pin "1") (pinfunction "B_1") (pintype "passive"))
    )
    (net (code "66") (name "Net-(U$2-PIN5_VADJ)") (class "Default")
      (node (ref "C6") (pin "2") (pinfunction "2_2") (pintype "passive"))
      (node (ref "R1") (pin "1") (pinfunction "1_1") (pintype "passive"))
      (node (ref "R2") (pin "2") (pinfunction "2_2") (pintype "passive"))
      (node (ref "U$2") (pin "5") (pinfunction "PIN5_VADJ_5") (pintype "bidirectional"))
    )
    (net (code "67") (name "Net-(U$5-STBY)") (class "Default")
      (node (ref "R4") (pin "1") (pinfunction "1_1") (pintype "passive"))
      (node (ref "U$5") (pin "P$8") (pinfunction "STBY_P$8") (pintype "bidirectional"))
    )
    (net (code "68") (name "Net-(U$8-PIN4_D2)") (class "Default")
      (node (ref "ES1") (pin "P$2") (pinfunction "P$2_P$2") (pintype "bidirectional"))
      (node (ref "U$8") (pin "4") (pinfunction "PIN4_D2_4") (pintype "bidirectional"))
    )
    (net (code "69") (name "Net-(U$8-PIN6_D1)") (class "Default")
      (node (ref "ES2") (pin "P$2") (pinfunction "P$2_P$2") (pintype "bidirectional"))
      (node (ref "U$8") (pin "6") (pinfunction "PIN6_D1_6") (pintype "bidirectional"))
    )
    (net (code "70") (name "Net-(U$9-PIN4_D2)") (class "Default")
      (node (ref "ES4") (pin "P$2") (pinfunction "P$2_P$2") (pintype "bidirectional"))
      (node (ref "U$9") (pin "4") (pinfunction "PIN4_D2_4") (pintype "bidirectional"))
    )
    (net (code "71") (name "Net-(U$9-PIN6_D1)") (class "Default")
      (node (ref "ES3") (pin "P$2") (pinfunction "P$2_P$2") (pintype "bidirectional"))
      (node (ref "U$9") (pin "6") (pinfunction "PIN6_D1_6") (pintype "bidirectional"))
    )
    (net (code "72") (name "Net-(U$10-PIN4_D2)") (class "Default")
      (node (ref "ES5") (pin "P$2") (pinfunction "P$2_P$2") (pintype "bidirectional"))
      (node (ref "U$10") (pin "4") (pinfunction "PIN4_D2_4") (pintype "bidirectional"))
    )
    (net (code "73") (name "Net-(U$10-PIN6_D1)") (class "Default")
      (node (ref "ES6") (pin "P$2") (pinfunction "P$2_P$2") (pintype "bidirectional"))
      (node (ref "U$10") (pin "6") (pinfunction "PIN6_D1_6") (pintype "bidirectional"))
    )
    (net (code "74") (name "Net-(U$11-PIN4_D2)") (class "Default")
      (node (ref "ES8") (pin "P$2") (pinfunction "P$2_P$2") (pintype "bidirectional"))
      (node (ref "U$11") (pin "4") (pinfunction "PIN4_D2_4") (pintype "bidirectional"))
    )
    (net (code "75") (name "Net-(U$11-PIN6_D1)") (class "Default")
      (node (ref "ES7") (pin "P$2") (pinfunction "P$2_P$2") (pintype "bidirectional"))
      (node (ref "U$11") (pin "6") (pinfunction "PIN6_D1_6") (pintype "bidirectional"))
    )
    (net (code "76") (name "VCC") (class "Default")
      (node (ref "BOX10P-L2") (pin "P$10") (pinfunction "P$10_P$10") (pintype "bidirectional"))
      (node (ref "BOX10P-L2") (pin "P$9") (pinfunction "P$9_P$9") (pintype "bidirectional"))
      (node (ref "C14") (pin "1") (pinfunction "1_1") (pintype "passive"))
      (node (ref "C3") (pin "1") (pinfunction "1_1") (pintype "passive"))
      (node (ref "U$2") (pin "1") (pinfunction "PIN1_CON_1") (pintype "bidirectional"))
      (node (ref "U$2") (pin "6") (pinfunction "PIN6_VIN_6") (pintype "bidirectional"))
      (node (ref "U$3") (pin "2") (pinfunction "C_2") (pintype "passive"))
      (node (ref "U$3") (pin "2@2") (pinfunction "C_2@2") (pintype "passive"))
      (node (ref "U$5") (pin "P$3") (pinfunction "VDD_P$3") (pintype "bidirectional"))
    )
    (net (code "77") (name "VDD") (class "Default")
      (node (ref "C11") (pin "1") (pinfunction "1_1") (pintype "passive"))
      (node (ref "C12") (pin "1") (pinfunction "1_1") (pintype "passive"))
      (node (ref "C13") (pin "1") (pinfunction "1_1") (pintype "passive"))
      (node (ref "ES1") (pin "P$1") (pinfunction "P$1_P$1") (pintype "bidirectional"))
      (node (ref "ES2") (pin "P$1") (pinfunction "P$1_P$1") (pintype "bidirectional"))
      (node (ref "ES3") (pin "P$1") (pinfunction "P$1_P$1") (pintype "bidirectional"))
      (node (ref "ES4") (pin "P$1") (pinfunction "P$1_P$1") (pintype "bidirectional"))
      (node (ref "ES5") (pin "P$1") (pinfunction "P$1_P$1") (pintype "bidirectional"))
      (node (ref "ES6") (pin "P$1") (pinfunction "P$1_P$1") (pintype "bidirectional"))
      (node (ref "ES7") (pin "P$1") (pinfunction "P$1_P$1") (pintype "bidirectional"))
      (node (ref "ES8") (pin "P$1") (pinfunction "P$1_P$1") (pintype "bidirectional"))
      (node (ref "LED1") (pin "A") (pinfunction "A_A") (pintype "passive"))
      (node (ref "NAND1") (pin "14") (pinfunction "VCC_14") (pintype "bidirectional"))
      (node (ref "NAND2") (pin "14") (pinfunction "VCC_14") (pintype "bidirectional"))
      (node (ref "R_I3") (pin "5") (pinfunction "5_5") (pintype "passive"))
      (node (ref "R_I3") (pin "6") (pinfunction "6_6") (pintype "passive"))
      (node (ref "R_I3") (pin "7") (pinfunction "7_7") (pintype "passive"))
      (node (ref "R_I3") (pin "8") (pinfunction "8_8") (pintype "passive"))
      (node (ref "R_I4") (pin "5") (pinfunction "5_5") (pintype "passive"))
      (node (ref "R_I4") (pin "6") (pinfunction "6_6") (pintype "passive"))
      (node (ref "R_I4") (pin "7") (pinfunction "7_7") (pintype "passive"))
      (node (ref "R_I4") (pin "8") (pinfunction "8_8") (pintype "passive"))
      (node (ref "U$12") (pin "P$2") (pinfunction "P$2_P$2") (pintype "bidirectional"))
      (node (ref "U$21") (pin "+") (pinfunction "+_+") (pintype "passive"))
    )
    (net (code "78") (name "unconnected-(BOX10P-L2-PadP$3)") (class "Default")
      (node (ref "BOX10P-L2") (pin "P$3") (pinfunction "P$3_P$3") (pintype "bidirectional"))
    )
    (net (code "79") (name "unconnected-(BOX10P-L2-PadP$4)") (class "Default")
      (node (ref "BOX10P-L2") (pin "P$4") (pinfunction "P$4_P$4") (pintype "bidirectional"))
    )
    (net (code "80") (name "unconnected-(R_I5-Pad3)") (class "Default")
      (node (ref "R_I5") (pin "3") (pinfunction "3_3") (pintype "passive"))
    )
    (net (code "81") (name "unconnected-(R_I5-Pad6)") (class "Default")
      (node (ref "R_I5") (pin "6") (pinfunction "6_6") (pintype "passive"))
    )
    (net (code "82") (name "unconnected-(U$1-PIN6-Pad6)") (class "Default")
      (node (ref "U$1") (pin "6") (pinfunction "PIN6_6") (pintype "bidirectional"))
    )
    (net (code "83") (name "unconnected-(U$1-PIN7-Pad7)") (class "Default")
      (node (ref "U$1") (pin "7") (pinfunction "PIN7_7") (pintype "bidirectional"))
    )
    (net (code "84") (name "unconnected-(U$1-PIN8-Pad8)") (class "Default")
      (node (ref "U$1") (pin "8") (pinfunction "PIN8_8") (pintype "bidirectional"))
    )
    (net (code "85") (name "unconnected-(U$1-PIN19-Pad19)") (class "Default")
      (node (ref "U$1") (pin "19") (pinfunction "PIN19_19") (pintype "bidirectional"))
    )
    (net (code "86") (name "unconnected-(U$1-PIN20-Pad20)") (class "Default")
      (node (ref "U$1") (pin "20") (pinfunction "PIN20_20") (pintype "bidirectional"))
    )
    (net (code "87") (name "unconnected-(U$4-NC-PadP$3)") (class "Default")
      (node (ref "U$4") (pin "P$3") (pinfunction "NC_P$3") (pintype "bidirectional"))
    )
    (net (code "88") (name "unconnected-(U$4-NC-PadP$4)") (class "Default")
      (node (ref "U$4") (pin "P$4") (pinfunction "NC_P$4") (pintype "bidirectional"))
    )
    (net (code "89") (name "unconnected-(U$22-P$1-Pad1)") (class "Default")
      (node (ref "U$22") (pin "1") (pinfunction "P$1_1") (pintype "bidirectional"))
    )
    (net (code "90") (name "unconnected-(U$22-P$2-Pad2)") (class "Default")
      (node (ref "U$22") (pin "2") (pinfunction "P$2_2") (pintype "bidirectional"))
    )
    (net (code "91") (name "unconnected-(U$22-P$9-Pad9)") (class "Default")
      (node (ref "U$22") (pin "9") (pinfunction "P$9_9") (pintype "bidirectional"))
    )
  )
)
